# Sheet2.net
KiCad netlist of a schematic drawn in Altium Designer
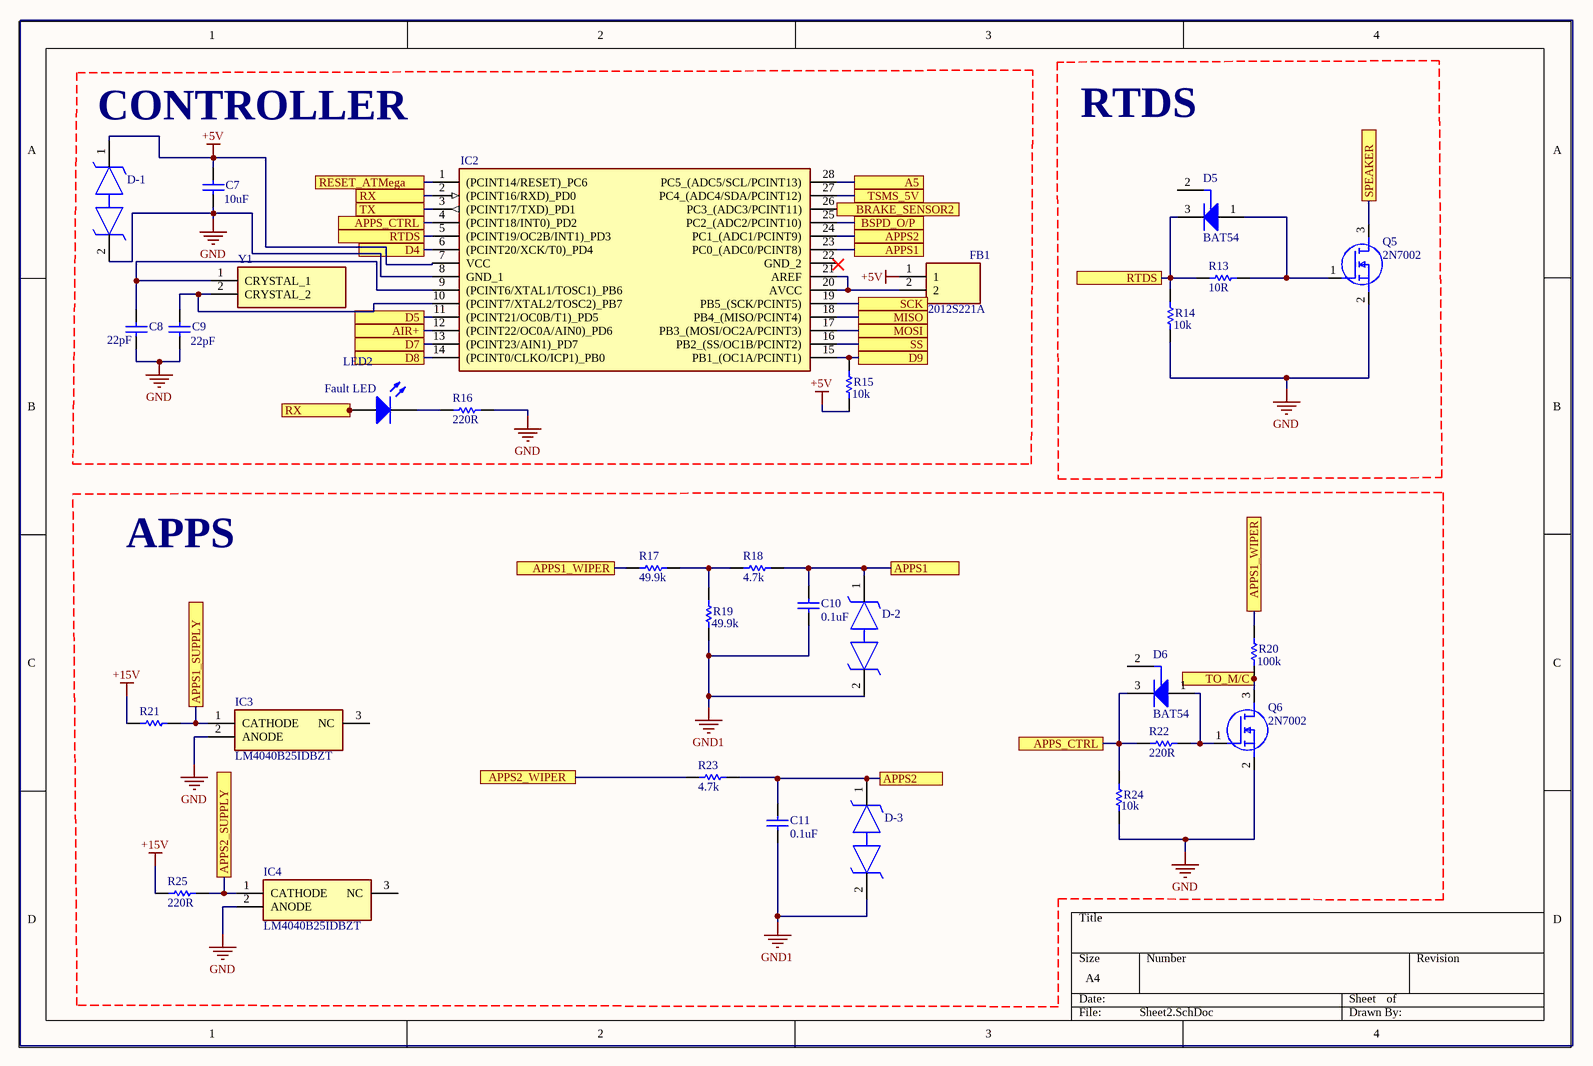
[diagram p0: Sheet2.SchDoc]

(export (version "E")
  (design (tool "Eeschema 10.0.6"))
  (components
    (comp (ref "C7")
      (value "10uF")
      (footprint "KEMT-1206-2_N")
      (description "CAP, Ceramic, 0.1 uF, +/- 10%, 50 V, -55 to 125 degC, 1206 (3216 Metric), RoHS, Tape and Reel")
      (fields (field (name "MANUFACTURER") "Kemet"))
      (libsource (lib "Schlib1_TSAL_LV_3.1") (part "CMP-1037-04202-2"))
    )
    (comp (ref "C8")
      (value "22pF")
      (footprint "KEMT-1206-2_N")
      (description "CAP, Ceramic, 0.1 uF, +/- 10%, 50 V, -55 to 125 degC, 1206 (3216 Metric), RoHS, Tape and Reel")
      (fields (field (name "MANUFACTURER") "Kemet"))
      (libsource (lib "Schlib1_TSAL_LV_3.1") (part "CMP-1037-04202-2"))
    )
    (comp (ref "C9")
      (value "22pF")
      (footprint "KEMT-1206-2_N")
      (description "CAP, Ceramic, 0.1 uF, +/- 10%, 50 V, -55 to 125 degC, 1206 (3216 Metric), RoHS, Tape and Reel")
      (fields (field (name "MANUFACTURER") "Kemet"))
      (libsource (lib "Schlib1_TSAL_LV_3.1") (part "CMP-1037-04202-2"))
    )
    (comp (ref "C10")
      (value "0.1uF")
      (footprint "KEMT-1206-2_N")
      (description "CAP, Ceramic, 0.1 uF, +/- 10%, 50 V, -55 to 125 degC, 1206 (3216 Metric), RoHS, Tape and Reel")
      (fields (field (name "MANUFACTURER") "Kemet"))
      (libsource (lib "Schlib1") (part "CMP-1037-04202-2"))
    )
    (comp (ref "C11")
      (value "0.1uF")
      (footprint "KEMT-1206-2_N")
      (description "CAP, Ceramic, 0.1 uF, +/- 10%, 50 V, -55 to 125 degC, 1206 (3216 Metric), RoHS, Tape and Reel")
      (fields (field (name "MANUFACTURER") "Kemet"))
      (libsource (lib "Schlib1") (part "CMP-1037-04202-2"))
    )
    (comp (ref "D-1")
      (value "TPD1E6B06DPLR")
      (footprint "R1206")
      (libsource (lib "Diode_Texas_Instruments_TPD1E6B06DPLR_eec") (part "TPD1E6B06DPLR"))
    )
    (comp (ref "D-2")
      (value "TPD1E6B06DPLR")
      (footprint "R1206")
      (libsource (lib "Diode_Texas_Instruments_TPD1E6B06DPLR_eec") (part "TPD1E6B06DPLR"))
    )
    (comp (ref "D-3")
      (value "TPD1E6B06DPLR")
      (footprint "R1206")
      (libsource (lib "Diode_Texas_Instruments_TPD1E6B06DPLR_eec") (part "TPD1E6B06DPLR"))
    )
    (comp (ref "D5")
      (value "BAT54")
      (footprint "INF-SOT23_N")
      (description "Silicon Schottky Diode, SOT23, Reel, Green")
      (fields (field (name "MANUFACTURER") "Infineon"))
      (libsource (lib "Schlib1") (part "CMP-1182-00010-1"))
    )
    (comp (ref "D6")
      (value "BAT54")
      (footprint "INF-SOT23_N")
      (description "Silicon Schottky Diode, SOT23, Reel, Green")
      (fields (field (name "MANUFACTURER") "Infineon"))
      (libsource (lib "Schlib1") (part "CMP-1182-00010-1"))
    )
    (comp (ref "Fault LED")
      (value "LED2")
      (footprint "3.2X1.6X1.1")
      (description "Typical RED, GREEN, YELLOW, AMBER GaAs LED")
      (fields (field (name "PUBLISHER") "Altium Limited"))
      (libsource (lib "Miscellaneous Devices") (part "LED2"))
    )
    (comp (ref "FB1")
      (value "MPZ2012S221A")
      (footprint "SamacSys:BEADC2012X105N")
      (description "Ferrite Bead")
      (fields (field (name "MOUSER PART NUMBER") "810-MPZ2012S221A"))
      (libsource (lib "SamacSys") (part "MPZ2012S221A"))
    )
    (comp (ref "IC2")
      (value "ATMEGA328-PU")
      (footprint "SamacSys:DIP1016W53P254L3468H457Q28N")
      (description "Integrated Circuit")
      (fields (field (name "MOUSER PART NUMBER") "556-ATMEGA328-PU"))
      (libsource (lib "SamacSys") (part "ATMEGA328-PU"))
    )
    (comp (ref "IC3")
      (value "LM4040B25IDBZT")
      (footprint "SamacSys:SOT95P237X112-3N")
      (description "Integrated Circuit")
      (fields (field (name "MOUSER PART NUMBER") "595-LM4040B25IDBZT"))
      (libsource (lib "SamacSys") (part "LM4040B25IDBZT"))
    )
    (comp (ref "IC4")
      (value "LM4040B25IDBZT")
      (footprint "SamacSys:SOT95P237X112-3N")
      (description "Integrated Circuit")
      (fields (field (name "MOUSER PART NUMBER") "595-LM4040B25IDBZT"))
      (libsource (lib "SamacSys") (part "LM4040B25IDBZT"))
    )
    (comp (ref "Q5")
      (value "2N7002")
      (footprint "SamacSys:SOT96P240X120-3N")
      (description "MOSFET (N-Channel)")
      (fields (field (name "MOUSER PART NUMBER") "781-2N7002"))
      (libsource (lib "SamacSys") (part "2N7002"))
    )
    (comp (ref "Q6")
      (value "2N7002")
      (footprint "SamacSys:SOT96P240X120-3N")
      (description "MOSFET (N-Channel)")
      (fields (field (name "MOUSER PART NUMBER") "781-2N7002"))
      (libsource (lib "SamacSys") (part "2N7002"))
    )
    (comp (ref "R13")
      (value "10R")
      (footprint "RESC3216X60X45NL10T20 - duplicate")
      (fields (field (name "PART NUMBER") "CRCW120647K0FKEA") (field (name "MANUFACTURER") "Vishay Dale"))
      (libsource (lib "Schlib1") (part "CMP-2003-02213-1"))
    )
    (comp (ref "R14")
      (value "10k")
      (footprint "RESC3216X60X45NL10T20 - duplicate")
      (fields (field (name "PART NUMBER") "CRCW120647K0FKEA") (field (name "MANUFACTURER") "Vishay Dale"))
      (libsource (lib "Schlib1") (part "CMP-2003-02213-1"))
    )
    (comp (ref "R15")
      (value "10k")
      (footprint "RESC3216X60X45NL10T20 - duplicate")
      (fields (field (name "PART NUMBER") "CRCW120647K0FKEA") (field (name "MANUFACTURER") "Vishay Dale"))
      (libsource (lib "Schlib1") (part "CMP-2003-02213-1"))
    )
    (comp (ref "R16")
      (value "220R")
      (footprint "RESC3216X60X45NL10T20 - duplicate")
      (fields (field (name "PART NUMBER") "CRCW120647K0FKEA") (field (name "MANUFACTURER") "Vishay Dale"))
      (libsource (lib "Schlib1") (part "CMP-2003-02213-1"))
    )
    (comp (ref "R17")
      (value "49.9k")
      (footprint "RESC3216X60X45NL10T20 - duplicate")
      (fields (field (name "PART NUMBER") "CRCW120647K0FKEA") (field (name "MANUFACTURER") "Vishay Dale"))
      (libsource (lib "Schlib1") (part "CMP-2003-02213-1"))
    )
    (comp (ref "R18")
      (value "4.7k")
      (footprint "RESC3216X60X45NL10T20 - duplicate")
      (fields (field (name "PART NUMBER") "CRCW120647K0FKEA") (field (name "MANUFACTURER") "Vishay Dale"))
      (libsource (lib "Schlib1") (part "CMP-2003-02213-1"))
    )
    (comp (ref "R19")
      (value "49.9k")
      (footprint "RESC3216X60X45NL10T20 - duplicate")
      (fields (field (name "PART NUMBER") "CRCW120647K0FKEA") (field (name "MANUFACTURER") "Vishay Dale"))
      (libsource (lib "Schlib1") (part "CMP-2003-02213-1"))
    )
    (comp (ref "R20")
      (value "100k")
      (footprint "RESC3216X60X45NL10T20 - duplicate")
      (fields (field (name "PART NUMBER") "CRCW120647K0FKEA") (field (name "MANUFACTURER") "Vishay Dale"))
      (libsource (lib "Schlib1") (part "CMP-2003-02213-1"))
    )
    (comp (ref "R21")
      (value "CRCW120647K0FKEA")
      (footprint "RESC3216X60X45NL10T20 - duplicate")
      (fields (field (name "MANUFACTURER") "Vishay Dale"))
      (libsource (lib "Schlib1") (part "CMP-2003-02213-1"))
    )
    (comp (ref "R22")
      (value "220R")
      (footprint "RESC3216X60X45NL10T20 - duplicate")
      (fields (field (name "PART NUMBER") "CRCW120647K0FKEA") (field (name "MANUFACTURER") "Vishay Dale"))
      (libsource (lib "Schlib1") (part "CMP-2003-02213-1"))
    )
    (comp (ref "R23")
      (value "4.7k")
      (footprint "RESC3216X60X45NL10T20 - duplicate")
      (fields (field (name "PART NUMBER") "CRCW120647K0FKEA") (field (name "MANUFACTURER") "Vishay Dale"))
      (libsource (lib "Schlib1") (part "CMP-2003-02213-1"))
    )
    (comp (ref "R24")
      (value "10k")
      (footprint "RESC3216X60X45NL10T20 - duplicate")
      (fields (field (name "PART NUMBER") "CRCW120647K0FKEA") (field (name "MANUFACTURER") "Vishay Dale"))
      (libsource (lib "Schlib1") (part "CMP-2003-02213-1"))
    )
    (comp (ref "R25")
      (value "220R")
      (footprint "RESC3216X60X45NL10T20 - duplicate")
      (fields (field (name "PART NUMBER") "CRCW120647K0FKEA") (field (name "MANUFACTURER") "Vishay Dale"))
      (libsource (lib "Schlib1") (part "CMP-2003-02213-1"))
    )
    (comp (ref "Y1")
      (value "ECS-160-18-4X-CKM")
      (footprint "SamacSys:ECS160184XCKM")
      (description "Crystal or Oscillator")
      (fields (field (name "MOUSER PART NUMBER") "520-ECS160-18-4X-CKM"))
      (libsource (lib "SamacSys") (part "ECS-160-18-4X-CKM"))
    )
  )
  (nets
    (net (code "1") (name "+5V") (class "Default")
      (node (ref "C7") (pin "2") (pinfunction "2_2") (pintype "passive"))
      (node (ref "D-1") (pin "1") (pinfunction "1_1") (pintype "passive"))
      (node (ref "FB1") (pin "1") (pinfunction "1_1") (pintype "passive"))
      (node (ref "IC2") (pin "7") (pinfunction "VCC_7") (pintype "power_in"))
      (node (ref "R15") (pin "1") (pinfunction "1_1") (pintype "passive"))
    )
    (net (code "2") (name "+15V") (class "Default")
      (node (ref "R21") (pin "2") (pinfunction "2_2") (pintype "passive"))
      (node (ref "R25") (pin "2") (pinfunction "2_2") (pintype "passive"))
    )
    (net (code "3") (name "/A5") (class "Default")
      (node (ref "IC2") (pin "28") (pinfunction "PC5_(ADC5/SCL/PCINT13)_28") (pintype "passive"))
    )
    (net (code "4") (name "/AIR+") (class "Default")
      (node (ref "IC2") (pin "12") (pinfunction "(PCINT22/OC0A/AIN0)_PD6_12") (pintype "passive"))
    )
    (net (code "5") (name "/APPS1") (class "Default")
      (node (ref "C10") (pin "2") (pinfunction "2_2") (pintype "passive"))
      (node (ref "D-2") (pin "1") (pinfunction "1_1") (pintype "passive"))
      (node (ref "IC2") (pin "23") (pinfunction "PC0_(ADC0/PCINT8)_23") (pintype "passive"))
      (node (ref "R18") (pin "1") (pinfunction "1_1") (pintype "passive"))
    )
    (net (code "6") (name "/APPS1_SUPPLY") (class "Default")
      (node (ref "IC3") (pin "1") (pinfunction "CATHODE_1") (pintype "passive"))
      (node (ref "R21") (pin "1") (pinfunction "1_1") (pintype "passive"))
    )
    (net (code "7") (name "/APPS1_WIPER") (class "Default")
      (node (ref "R17") (pin "2") (pinfunction "2_2") (pintype "passive"))
      (node (ref "R20") (pin "2") (pinfunction "2_2") (pintype "passive"))
    )
    (net (code "8") (name "/APPS2") (class "Default")
      (node (ref "C11") (pin "2") (pinfunction "2_2") (pintype "passive"))
      (node (ref "D-3") (pin "1") (pinfunction "1_1") (pintype "passive"))
      (node (ref "IC2") (pin "24") (pinfunction "PC1_(ADC1/PCINT9)_24") (pintype "passive"))
      (node (ref "R23") (pin "1") (pinfunction "1_1") (pintype "passive"))
    )
    (net (code "9") (name "/APPS2_SUPPLY") (class "Default")
      (node (ref "IC4") (pin "1") (pinfunction "CATHODE_1") (pintype "passive"))
      (node (ref "R25") (pin "1") (pinfunction "1_1") (pintype "passive"))
    )
    (net (code "10") (name "/APPS2_WIPER") (class "Default")
      (node (ref "R23") (pin "2") (pinfunction "2_2") (pintype "passive"))
    )
    (net (code "11") (name "/APPS_CTRL") (class "Default")
      (node (ref "D6") (pin "3") (pinfunction "K_3") (pintype "passive"))
      (node (ref "IC2") (pin "4") (pinfunction "(PCINT18/INT0)_PD2_4") (pintype "passive"))
      (node (ref "R22") (pin "2") (pinfunction "2_2") (pintype "passive"))
      (node (ref "R24") (pin "2") (pinfunction "2_2") (pintype "passive"))
    )
    (net (code "12") (name "/BRAKE_SENSOR2") (class "Default")
      (node (ref "IC2") (pin "26") (pinfunction "PC3_(ADC3/PCINT11)_26") (pintype "passive"))
    )
    (net (code "13") (name "/BSPD_O{slash}P") (class "Default")
      (node (ref "IC2") (pin "25") (pinfunction "PC2_(ADC2/PCINT10)_25") (pintype "passive"))
    )
    (net (code "14") (name "/D4") (class "Default")
      (node (ref "IC2") (pin "6") (pinfunction "(PCINT20/XCK/T0)_PD4_6") (pintype "passive"))
    )
    (net (code "15") (name "/D5") (class "Default")
      (node (ref "IC2") (pin "11") (pinfunction "(PCINT21/OC0B/T1)_PD5_11") (pintype "passive"))
    )
    (net (code "16") (name "/D7") (class "Default")
      (node (ref "IC2") (pin "13") (pinfunction "(PCINT23/AIN1)_PD7_13") (pintype "passive"))
    )
    (net (code "17") (name "/D8") (class "Default")
      (node (ref "IC2") (pin "14") (pinfunction "(PCINT0/CLKO/ICP1)_PB0_14") (pintype "passive"))
    )
    (net (code "18") (name "/D9") (class "Default")
      (node (ref "IC2") (pin "15") (pinfunction "PB1_(OC1A/PCINT1)_15") (pintype "passive"))
      (node (ref "R15") (pin "2") (pinfunction "2_2") (pintype "passive"))
    )
    (net (code "19") (name "/MISO") (class "Default")
      (node (ref "IC2") (pin "18") (pinfunction "PB4_(MISO/PCINT4)_18") (pintype "passive"))
    )
    (net (code "20") (name "/MOSI") (class "Default")
      (node (ref "IC2") (pin "17") (pinfunction "PB3_(MOSI/OC2A/PCINT3)_17") (pintype "passive"))
    )
    (net (code "21") (name "/RESET_ATMega") (class "Default")
      (node (ref "IC2") (pin "1") (pinfunction "(PCINT14/RESET)_PC6_1") (pintype "passive"))
    )
    (net (code "22") (name "/RTDS") (class "Default")
      (node (ref "D5") (pin "3") (pinfunction "K_3") (pintype "passive"))
      (node (ref "IC2") (pin "5") (pinfunction "(PCINT19/OC2B/INT1)_PD3_5") (pintype "passive"))
      (node (ref "R13") (pin "2") (pinfunction "2_2") (pintype "passive"))
      (node (ref "R14") (pin "2") (pinfunction "2_2") (pintype "passive"))
    )
    (net (code "23") (name "/RX") (class "Default")
      (node (ref "Fault LED") (pin "1") (pinfunction "A_1") (pintype "passive"))
      (node (ref "IC2") (pin "2") (pinfunction "(PCINT16/RXD)_PD0_2") (pintype "input"))
    )
    (net (code "24") (name "/SCK") (class "Default")
      (node (ref "IC2") (pin "19") (pinfunction "PB5_(SCK/PCINT5)_19") (pintype "passive"))
    )
    (net (code "25") (name "/SPEAKER") (class "Default")
      (node (ref "Q5") (pin "3") (pinfunction "D_3") (pintype "passive"))
    )
    (net (code "26") (name "/SS") (class "Default")
      (node (ref "IC2") (pin "16") (pinfunction "PB2_(SS/OC1B/PCINT2)_16") (pintype "passive"))
    )
    (net (code "27") (name "/TO_M{slash}C") (class "Default")
      (node (ref "Q6") (pin "3") (pinfunction "D_3") (pintype "passive"))
      (node (ref "R20") (pin "1") (pinfunction "1_1") (pintype "passive"))
    )
    (net (code "28") (name "/TSMS_5V") (class "Default")
      (node (ref "IC2") (pin "27") (pinfunction "PC4_(ADC4/SDA/PCINT12)_27") (pintype "passive"))
    )
    (net (code "29") (name "/TX") (class "Default")
      (node (ref "IC2") (pin "3") (pinfunction "(PCINT17/TXD)_PD1_3") (pintype "output"))
    )
    (net (code "30") (name "GND") (class "Default")
      (node (ref "C7") (pin "1") (pinfunction "1_1") (pintype "passive"))
      (node (ref "C8") (pin "1") (pinfunction "1_1") (pintype "passive"))
      (node (ref "C9") (pin "1") (pinfunction "1_1") (pintype "passive"))
      (node (ref "D-1") (pin "2") (pinfunction "2_2") (pintype "passive"))
      (node (ref "IC2") (pin "8") (pinfunction "GND_1_8") (pintype "power_in"))
      (node (ref "IC3") (pin "2") (pinfunction "ANODE_2") (pintype "passive"))
      (node (ref "IC4") (pin "2") (pinfunction "ANODE_2") (pintype "passive"))
      (node (ref "Q5") (pin "2") (pinfunction "S_2") (pintype "passive"))
      (node (ref "Q6") (pin "2") (pinfunction "S_2") (pintype "passive"))
      (node (ref "R14") (pin "1") (pinfunction "1_1") (pintype "passive"))
      (node (ref "R16") (pin "1") (pinfunction "1_1") (pintype "passive"))
      (node (ref "R24") (pin "1") (pinfunction "1_1") (pintype "passive"))
    )
    (net (code "31") (name "GND1") (class "Default")
      (node (ref "C10") (pin "1") (pinfunction "1_1") (pintype "passive"))
      (node (ref "C11") (pin "1") (pinfunction "1_1") (pintype "passive"))
      (node (ref "D-2") (pin "2") (pinfunction "2_2") (pintype "passive"))
      (node (ref "D-3") (pin "2") (pinfunction "2_2") (pintype "passive"))
      (node (ref "R19") (pin "1") (pinfunction "1_1") (pintype "passive"))
    )
    (net (code "32") (name "Net-(D5-A)") (class "Default")
      (node (ref "D5") (pin "1") (pinfunction "A_1") (pintype "passive"))
      (node (ref "Q5") (pin "1") (pinfunction "G_1") (pintype "passive"))
      (node (ref "R13") (pin "1") (pinfunction "1_1") (pintype "passive"))
    )
    (net (code "33") (name "Net-(D6-A)") (class "Default")
      (node (ref "D6") (pin "1") (pinfunction "A_1") (pintype "passive"))
      (node (ref "Q6") (pin "1") (pinfunction "G_1") (pintype "passive"))
      (node (ref "R22") (pin "1") (pinfunction "1_1") (pintype "passive"))
    )
    (net (code "34") (name "Net-(Fault LED-K)") (class "Default")
      (node (ref "Fault LED") (pin "2") (pinfunction "K_2") (pintype "passive"))
      (node (ref "R16") (pin "2") (pinfunction "2_2") (pintype "passive"))
    )
    (net (code "35") (name "Net-(IC2-(PCINT6{slash}XTAL1{slash}TOSC1)_PB6)") (class "Default")
      (node (ref "C8") (pin "2") (pinfunction "2_2") (pintype "passive"))
      (node (ref "IC2") (pin "9") (pinfunction "(PCINT6/XTAL1/TOSC1)_PB6_9") (pintype "passive"))
      (node (ref "Y1") (pin "1") (pinfunction "CRYSTAL_1_1") (pintype "passive"))
    )
    (net (code "36") (name "Net-(IC2-(PCINT7{slash}XTAL2{slash}TOSC2)_PB7)") (class "Default")
      (node (ref "C9") (pin "2") (pinfunction "2_2") (pintype "passive"))
      (node (ref "IC2") (pin "10") (pinfunction "(PCINT7/XTAL2/TOSC2)_PB7_10") (pintype "passive"))
      (node (ref "Y1") (pin "2") (pinfunction "CRYSTAL_2_2") (pintype "passive"))
    )
    (net (code "37") (name "Net-(IC2-AREF)") (class "Default")
      (node (ref "FB1") (pin "2") (pinfunction "2_2") (pintype "passive"))
      (node (ref "IC2") (pin "20") (pinfunction "AVCC_20") (pintype "power_in"))
      (node (ref "IC2") (pin "21") (pinfunction "AREF_21") (pintype "passive"))
    )
    (net (code "38") (name "Net-(R17-Pad1)") (class "Default")
      (node (ref "R17") (pin "1") (pinfunction "1_1") (pintype "passive"))
      (node (ref "R18") (pin "2") (pinfunction "2_2") (pintype "passive"))
      (node (ref "R19") (pin "2") (pinfunction "2_2") (pintype "passive"))
    )
    (net (code "39") (name "unconnected-(D5-NC-Pad2)") (class "Default")
      (node (ref "D5") (pin "2") (pinfunction "NC_2") (pintype "passive"))
    )
    (net (code "40") (name "unconnected-(D6-NC-Pad2)") (class "Default")
      (node (ref "D6") (pin "2") (pinfunction "NC_2") (pintype "passive"))
    )
    (net (code "41") (name "unconnected-(IC2-GND_2-Pad22)") (class "Default")
      (node (ref "IC2") (pin "22") (pinfunction "GND_2_22") (pintype "power_in"))
    )
    (net (code "42") (name "unconnected-(IC3-NC-Pad3)") (class "Default")
      (node (ref "IC3") (pin "3") (pinfunction "NC_3") (pintype "passive"))
    )
    (net (code "43") (name "unconnected-(IC4-NC-Pad3)") (class "Default")
      (node (ref "IC4") (pin "3") (pinfunction "NC_3") (pintype "passive"))
    )
  )
)
